# PRG_v2_0.net
KiCad netlist of a schematic drawn in Altium Designer
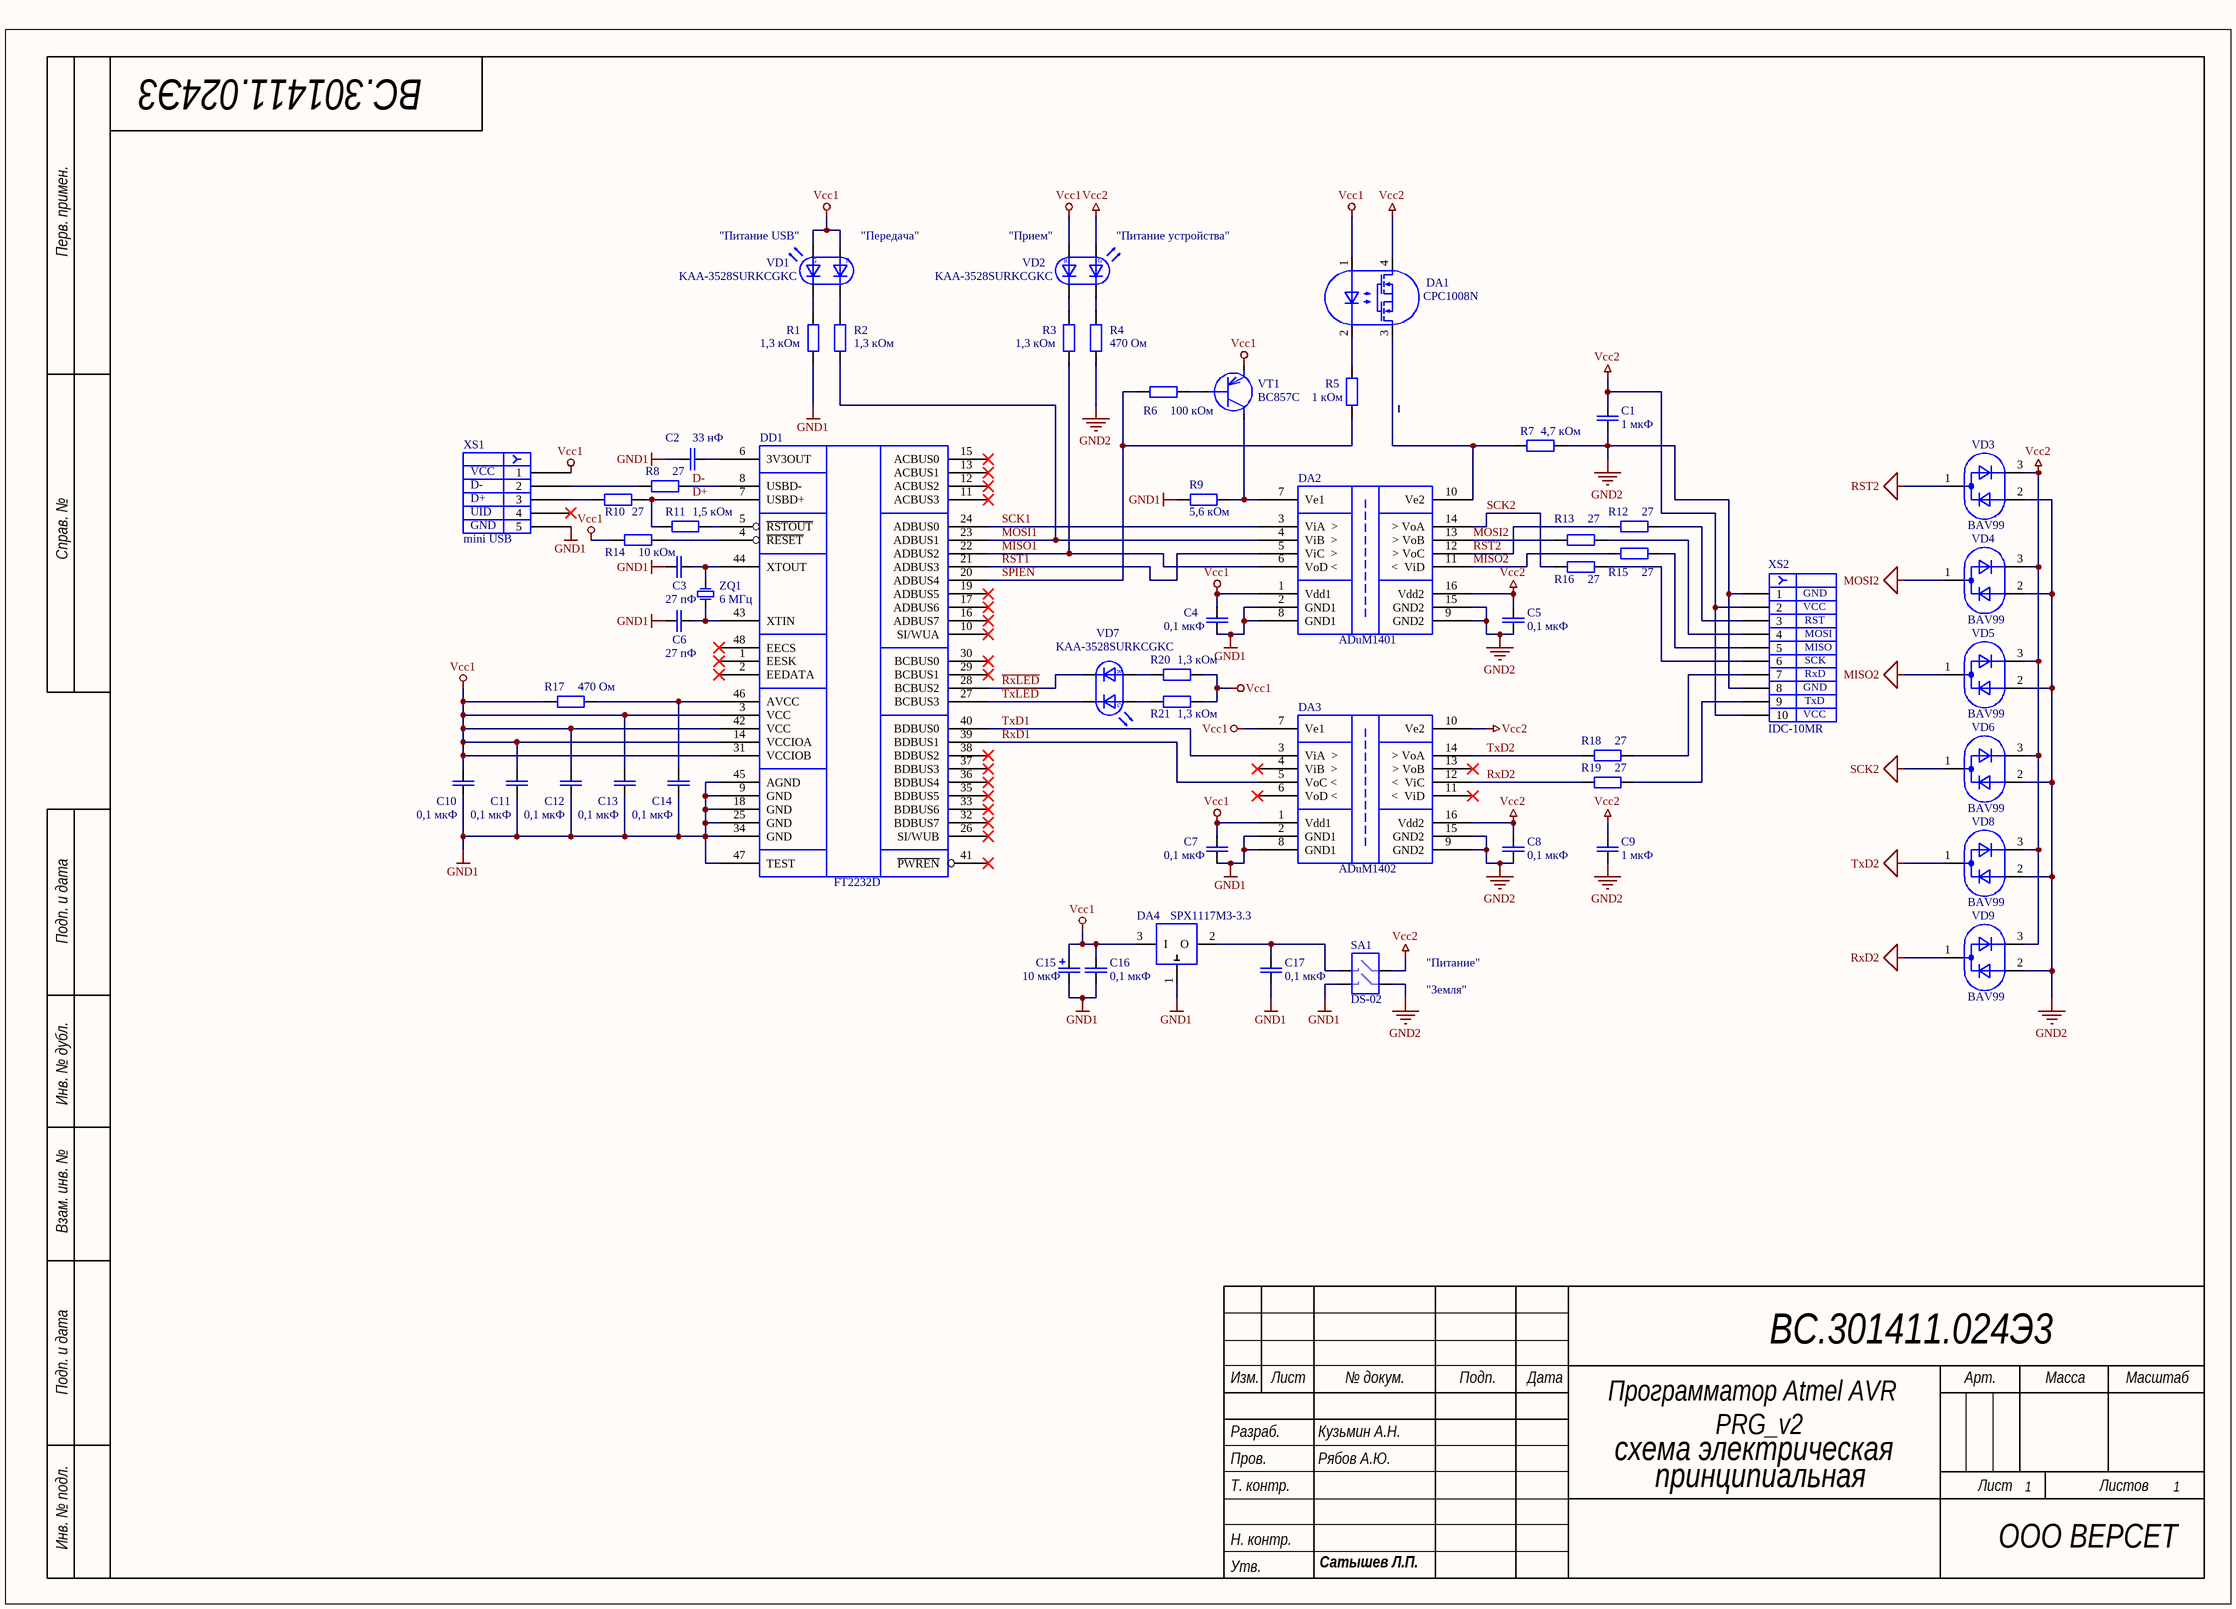
[diagram p0: PRG_v2.0.SchDoc]

(export (version "E")
  (design (tool "Eeschema 10.0.6"))
  (components
    (comp (ref "C1")
      (value "Конденсатор")
      (footprint "0603")
      (fields (field (name "НОМИНАЛ") "1 мкФ"))
      (libsource (lib "AVR-2232V") (part "C"))
    )
    (comp (ref "C2")
      (value "Конденсатор")
      (footprint "0603")
      (fields (field (name "НОМИНАЛ") "33 нФ"))
      (libsource (lib "AVR-2232V") (part "C"))
    )
    (comp (ref "C3")
      (value "Конденсатор")
      (footprint "0603")
      (fields (field (name "НОМИНАЛ") "27 пФ"))
      (libsource (lib "AVR-2232V") (part "C"))
    )
    (comp (ref "C4")
      (value "Конденсатор")
      (footprint "0603")
      (fields (field (name "НОМИНАЛ") "0,1 мкФ"))
      (libsource (lib "AVR-2232V") (part "C"))
    )
    (comp (ref "C5")
      (value "Конденсатор")
      (footprint "0603")
      (fields (field (name "НОМИНАЛ") "0,1 мкФ"))
      (libsource (lib "AVR-2232V") (part "C"))
    )
    (comp (ref "C6")
      (value "Конденсатор")
      (footprint "0603")
      (fields (field (name "НОМИНАЛ") "27 пФ"))
      (libsource (lib "AVR-2232V") (part "C"))
    )
    (comp (ref "C7")
      (value "Конденсатор")
      (footprint "0603")
      (fields (field (name "НОМИНАЛ") "0,1 мкФ"))
      (libsource (lib "AVR-2232V") (part "C"))
    )
    (comp (ref "C8")
      (value "Конденсатор")
      (footprint "0603")
      (fields (field (name "НОМИНАЛ") "0,1 мкФ"))
      (libsource (lib "AVR-2232V") (part "C"))
    )
    (comp (ref "C9")
      (value "Конденсатор")
      (footprint "0603")
      (fields (field (name "НОМИНАЛ") "1 мкФ"))
      (libsource (lib "AVR-2232V") (part "C"))
    )
    (comp (ref "C10")
      (value "Конденсатор")
      (footprint "0603")
      (fields (field (name "НОМИНАЛ") "0,1 мкФ"))
      (libsource (lib "AVR-2232V") (part "C"))
    )
    (comp (ref "C11")
      (value "Конденсатор")
      (footprint "0603")
      (fields (field (name "НОМИНАЛ") "0,1 мкФ"))
      (libsource (lib "AVR-2232V") (part "C"))
    )
    (comp (ref "C12")
      (value "Конденсатор")
      (footprint "0603")
      (fields (field (name "НОМИНАЛ") "0,1 мкФ"))
      (libsource (lib "AVR-2232V") (part "C"))
    )
    (comp (ref "C13")
      (value "Конденсатор")
      (footprint "0603")
      (fields (field (name "НОМИНАЛ") "0,1 мкФ"))
      (libsource (lib "AVR-2232V") (part "C"))
    )
    (comp (ref "C14")
      (value "Конденсатор")
      (footprint "0603")
      (fields (field (name "НОМИНАЛ") "0,1 мкФ"))
      (libsource (lib "AVR-2232V") (part "C"))
    )
    (comp (ref "C15")
      (value "Конденсатор электролитический")
      (footprint "C+A")
      (fields (field (name "НОМИНАЛ") "10 мкФ"))
      (libsource (lib "AVR-2232V") (part "C+"))
    )
    (comp (ref "C16")
      (value "Конденсатор")
      (footprint "0603")
      (fields (field (name "НОМИНАЛ") "0,1 мкФ"))
      (libsource (lib "AVR-2232V") (part "C"))
    )
    (comp (ref "C17")
      (value "Конденсатор")
      (footprint "0603")
      (fields (field (name "НОМИНАЛ") "0,1 мкФ"))
      (libsource (lib "AVR-2232V") (part "C"))
    )
    (comp (ref "DA1")
      (value "Оптопара")
      (footprint "SOIC4")
      (description "Оптореле")
      (libsource (lib "AVR-2232V") (part "CPC1008N"))
    )
    (comp (ref "DA2")
      (value "Буфер с гальванической разв зкой")
      (footprint "SOIC16")
      (libsource (lib "AVR-2232V") (part "ADuM1401"))
    )
    (comp (ref "DA3")
      (value "Буфер с гальванической разв зкой")
      (footprint "SOIC16")
      (libsource (lib "AVR-2232V") (part "ADuM1402"))
    )
    (comp (ref "DA4")
      (value "Стабилизатор напр жени ")
      (footprint "SOT223")
      (fields (field (name "TYPE") "SPX1117M3-3.3"))
      (libsource (lib "AVR-2232V") (part "VREG"))
    )
    (comp (ref "DD1")
      (value "Dual USB to Serial UART/FIFO IC")
      (footprint "LQFP48")
      (libsource (lib "AVR-2232V") (part "FT2232D"))
    )
    (comp (ref "R1")
      (value "Резистор")
      (footprint "0603")
      (fields (field (name "НОМИНАЛ") "1,3 кОм"))
      (libsource (lib "AVR-2232V") (part "R"))
    )
    (comp (ref "R2")
      (value "Резистор")
      (footprint "0603")
      (fields (field (name "НОМИНАЛ") "1,3 кОм"))
      (libsource (lib "AVR-2232V") (part "R"))
    )
    (comp (ref "R3")
      (value "Резистор")
      (footprint "0603")
      (fields (field (name "НОМИНАЛ") "1,3 кОм"))
      (libsource (lib "AVR-2232V") (part "R"))
    )
    (comp (ref "R4")
      (value "Резистор")
      (footprint "0603")
      (fields (field (name "НОМИНАЛ") "470 Ом"))
      (libsource (lib "AVR-2232V") (part "R"))
    )
    (comp (ref "R5")
      (value "Резистор")
      (footprint "0603")
      (fields (field (name "НОМИНАЛ") "1 кОм"))
      (libsource (lib "AVR-2232V") (part "R"))
    )
    (comp (ref "R6")
      (value "Резистор")
      (footprint "0603")
      (fields (field (name "НОМИНАЛ") "100 кОм"))
      (libsource (lib "AVR-2232V") (part "R"))
    )
    (comp (ref "R7")
      (value "Резистор")
      (footprint "0603")
      (fields (field (name "НОМИНАЛ") "4,7 кОм"))
      (libsource (lib "AVR-2232V") (part "R"))
    )
    (comp (ref "R8")
      (value "Резистор")
      (footprint "0603")
      (fields (field (name "НОМИНАЛ") "27"))
      (libsource (lib "AVR-2232V") (part "R"))
    )
    (comp (ref "R9")
      (value "Резистор")
      (footprint "0603")
      (fields (field (name "НОМИНАЛ") "5,6 кОм"))
      (libsource (lib "AVR-2232V") (part "R"))
    )
    (comp (ref "R10")
      (value "Резистор")
      (footprint "0603")
      (fields (field (name "НОМИНАЛ") "27"))
      (libsource (lib "AVR-2232V") (part "R"))
    )
    (comp (ref "R11")
      (value "Резистор")
      (footprint "0603")
      (fields (field (name "НОМИНАЛ") "1,5 кОм"))
      (libsource (lib "AVR-2232V") (part "R"))
    )
    (comp (ref "R12")
      (value "Резистор")
      (footprint "0603")
      (fields (field (name "НОМИНАЛ") "27"))
      (libsource (lib "AVR-2232V") (part "R"))
    )
    (comp (ref "R13")
      (value "Резистор")
      (footprint "0603")
      (fields (field (name "НОМИНАЛ") "27"))
      (libsource (lib "AVR-2232V") (part "R"))
    )
    (comp (ref "R14")
      (value "Резистор")
      (footprint "0603")
      (fields (field (name "НОМИНАЛ") "10 кОм"))
      (libsource (lib "AVR-2232V") (part "R"))
    )
    (comp (ref "R15")
      (value "Резистор")
      (footprint "0603")
      (fields (field (name "НОМИНАЛ") "27"))
      (libsource (lib "AVR-2232V") (part "R"))
    )
    (comp (ref "R16")
      (value "Резистор")
      (footprint "0603")
      (fields (field (name "НОМИНАЛ") "27"))
      (libsource (lib "AVR-2232V") (part "R"))
    )
    (comp (ref "R17")
      (value "Резистор")
      (footprint "0603")
      (fields (field (name "НОМИНАЛ") "470 Ом"))
      (libsource (lib "AVR-2232V") (part "R"))
    )
    (comp (ref "R18")
      (value "Резистор")
      (footprint "0603")
      (fields (field (name "НОМИНАЛ") "27"))
      (libsource (lib "AVR-2232V") (part "R"))
    )
    (comp (ref "R19")
      (value "Резистор")
      (footprint "0603")
      (fields (field (name "НОМИНАЛ") "27"))
      (libsource (lib "AVR-2232V") (part "R"))
    )
    (comp (ref "R20")
      (value "Резистор")
      (footprint "0603")
      (fields (field (name "НОМИНАЛ") "1,3 кОм"))
      (libsource (lib "AVR-2232V") (part "R"))
    )
    (comp (ref "R21")
      (value "Резистор")
      (footprint "0603")
      (fields (field (name "НОМИНАЛ") "1,3 кОм"))
      (libsource (lib "AVR-2232V") (part "R"))
    )
    (comp (ref "SA1")
      (value "Микропереключатель")
      (footprint "DS-02")
      (fields (field (name "ТИП") "DS-02"))
      (libsource (lib "AVR-2232V") (part "DS-02"))
    )
    (comp (ref "VD1")
      (value "Светодиод двухцветный")
      (footprint "KAA-3528SURKCGKC")
      (fields (field (name "ТИП") "KAA-3528SURKCGKC"))
      (libsource (lib "AVR-2232V") (part "Светодиод RG"))
    )
    (comp (ref "VD2")
      (value "Светодиод двухцветный")
      (footprint "KAA-3528SURKCGKC")
      (fields (field (name "ТИП") "KAA-3528SURKCGKC"))
      (libsource (lib "") (part "Светодиод RG_1"))
    )
    (comp (ref "VD3")
      (value "Пара защитный диодов Шоттки")
      (footprint "SOT23")
      (libsource (lib "AVR-2232V") (part "BAV99"))
    )
    (comp (ref "VD4")
      (value "Пара защитный диодов Шоттки")
      (footprint "SOT23")
      (libsource (lib "AVR-2232V") (part "BAV99"))
    )
    (comp (ref "VD5")
      (value "Пара защитный диодов Шоттки")
      (footprint "SOT23")
      (libsource (lib "AVR-2232V") (part "BAV99"))
    )
    (comp (ref "VD6")
      (value "Пара защитный диодов Шоттки")
      (footprint "SOT23")
      (libsource (lib "AVR-2232V") (part "BAV99"))
    )
    (comp (ref "VD7")
      (value "Светодиод двухцветный")
      (footprint "KAA-3528SURKCGKC")
      (fields (field (name "ТИП") "KAA-3528SURKCGKC"))
      (libsource (lib "") (part "Светодиод RG_1"))
    )
    (comp (ref "VD8")
      (value "Пара защитный диодов Шоттки")
      (footprint "SOT23")
      (libsource (lib "AVR-2232V") (part "BAV99"))
    )
    (comp (ref "VD9")
      (value "Пара защитный диодов Шоттки")
      (footprint "SOT23")
      (libsource (lib "AVR-2232V") (part "BAV99"))
    )
    (comp (ref "VT1")
      (value "Транзистор pnp")
      (footprint "SOT23")
      (fields (field (name "TYPE") "BC857C"))
      (libsource (lib "AVR-2232V") (part "PNP"))
    )
    (comp (ref "XS1")
      (value "Разъем мини-USB")
      (footprint "mini USB A")
      (libsource (lib "AVR-2232V") (part "miniUSB"))
    )
    (comp (ref "XS2")
      (value "IDC-10MR")
      (footprint "IDC-10MR")
      (fields (field (name "ТИП") "IDC-10MR"))
      (libsource (lib "AVR-2232V") (part "IDC-10MR"))
    )
    (comp (ref "ZQ1")
      (value "Кварцевый резонатор")
      (footprint "HC49-SM")
      (fields (field (name "НОМИНАЛ") "6 МГц"))
      (libsource (lib "AVR-2232V") (part "ZQ"))
    )
  )
  (nets
    (net (code "1") (name "/D+") (class "Default")
      (node (ref "DD1") (pin "7") (pinfunction "USBD+_7") (pintype "passive"))
      (node (ref "R10") (pin "2") (pinfunction "2_2") (pintype "passive"))
      (node (ref "R11") (pin "1") (pinfunction "1_1") (pintype "passive"))
    )
    (net (code "2") (name "/D-") (class "Default")
      (node (ref "DD1") (pin "8") (pinfunction "USBD-_8") (pintype "passive"))
      (node (ref "R8") (pin "2") (pinfunction "2_2") (pintype "passive"))
    )
    (net (code "3") (name "/MISO1") (class "Default")
      (node (ref "DA2") (pin "6") (pinfunction "VoD_<_6") (pintype "passive"))
      (node (ref "DD1") (pin "22") (pinfunction "ADBUS2_22") (pintype "passive"))
      (node (ref "R3") (pin "1") (pinfunction "1_1") (pintype "passive"))
    )
    (net (code "4") (name "/MOSI1") (class "Default")
      (node (ref "DA2") (pin "4") (pinfunction "ViB__>_4") (pintype "passive"))
      (node (ref "DD1") (pin "23") (pinfunction "ADBUS1_23") (pintype "passive"))
      (node (ref "R2") (pin "1") (pinfunction "1_1") (pintype "passive"))
    )
    (net (code "5") (name "/RxD1") (class "Default")
      (node (ref "DA3") (pin "5") (pinfunction "VoC_<_5") (pintype "passive"))
      (node (ref "DD1") (pin "39") (pinfunction "BDBUS1_39") (pintype "passive"))
    )
    (net (code "6") (name "/SCK1") (class "Default")
      (node (ref "DA2") (pin "3") (pinfunction "ViA__>_3") (pintype "passive"))
      (node (ref "DD1") (pin "24") (pinfunction "ADBUS0_24") (pintype "passive"))
    )
    (net (code "7") (name "/TxD1") (class "Default")
      (node (ref "DA3") (pin "3") (pinfunction "ViA__>_3") (pintype "passive"))
      (node (ref "DD1") (pin "40") (pinfunction "BDBUS0_40") (pintype "passive"))
    )
    (net (code "8") (name "/~{RST}1") (class "Default")
      (node (ref "DA2") (pin "5") (pinfunction "ViC__>_5") (pintype "passive"))
      (node (ref "DD1") (pin "21") (pinfunction "ADBUS3_21") (pintype "passive"))
    )
    (net (code "9") (name "/~{RxLED}") (class "Default")
      (node (ref "DD1") (pin "28") (pinfunction "BCBUS2_28") (pintype "passive"))
      (node (ref "VD7") (pin "1") (pinfunction "1_1") (pintype "passive"))
    )
    (net (code "10") (name "/~{SPIEN}") (class "Default")
      (node (ref "DD1") (pin "20") (pinfunction "ADBUS4_20") (pintype "passive"))
      (node (ref "R5") (pin "1") (pinfunction "1_1") (pintype "passive"))
      (node (ref "R6") (pin "2") (pinfunction "2_2") (pintype "passive"))
    )
    (net (code "11") (name "/~{TxLED}") (class "Default")
      (node (ref "DD1") (pin "27") (pinfunction "BCBUS3_27") (pintype "passive"))
      (node (ref "VD7") (pin "3") (pinfunction "3_3") (pintype "passive"))
    )
    (net (code "12") (name "GND1") (class "Default")
      (node (ref "C10") (pin "2") (pinfunction "2_2") (pintype "passive"))
      (node (ref "C11") (pin "2") (pinfunction "2_2") (pintype "passive"))
      (node (ref "C12") (pin "2") (pinfunction "2_2") (pintype "passive"))
      (node (ref "C13") (pin "2") (pinfunction "2_2") (pintype "passive"))
      (node (ref "C14") (pin "2") (pinfunction "2_2") (pintype "passive"))
      (node (ref "C15") (pin "2") (pinfunction "2_2") (pintype "passive"))
      (node (ref "C16") (pin "1") (pinfunction "1_1") (pintype "passive"))
      (node (ref "C17") (pin "1") (pinfunction "1_1") (pintype "passive"))
      (node (ref "C2") (pin "1") (pinfunction "1_1") (pintype "passive"))
      (node (ref "C3") (pin "1") (pinfunction "1_1") (pintype "passive"))
      (node (ref "C4") (pin "1") (pinfunction "1_1") (pintype "passive"))
      (node (ref "C6") (pin "1") (pinfunction "1_1") (pintype "passive"))
      (node (ref "C7") (pin "1") (pinfunction "1_1") (pintype "passive"))
      (node (ref "DA2") (pin "2") (pinfunction "GND1_2") (pintype "passive"))
      (node (ref "DA2") (pin "8") (pinfunction "GND1_8") (pintype "passive"))
      (node (ref "DA3") (pin "2") (pinfunction "GND1_2") (pintype "passive"))
      (node (ref "DA3") (pin "8") (pinfunction "GND1_8") (pintype "passive"))
      (node (ref "DA4") (pin "1") (pinfunction "GND_1") (pintype "passive"))
      (node (ref "DD1") (pin "18") (pinfunction "GND_18") (pintype "passive"))
      (node (ref "DD1") (pin "25") (pinfunction "GND_25") (pintype "passive"))
      (node (ref "DD1") (pin "34") (pinfunction "GND_34") (pintype "passive"))
      (node (ref "DD1") (pin "45") (pinfunction "AGND_45") (pintype "passive"))
      (node (ref "DD1") (pin "47") (pinfunction "TEST_47") (pintype "passive"))
      (node (ref "DD1") (pin "9") (pinfunction "GND_9") (pintype "passive"))
      (node (ref "R1") (pin "1") (pinfunction "1_1") (pintype "passive"))
      (node (ref "R9") (pin "2") (pinfunction "2_2") (pintype "passive"))
      (node (ref "SA1") (pin "4") (pinfunction "4_4") (pintype "passive"))
      (node (ref "XS1") (pin "5") (pinfunction "5_5") (pintype "passive"))
    )
    (net (code "13") (name "GND2") (class "Default")
      (node (ref "C1") (pin "1") (pinfunction "1_1") (pintype "passive"))
      (node (ref "C5") (pin "1") (pinfunction "1_1") (pintype "passive"))
      (node (ref "C8") (pin "1") (pinfunction "1_1") (pintype "passive"))
      (node (ref "C9") (pin "1") (pinfunction "1_1") (pintype "passive"))
      (node (ref "DA2") (pin "15") (pinfunction "GND2_15") (pintype "passive"))
      (node (ref "DA2") (pin "9") (pinfunction "GND2_9") (pintype "passive"))
      (node (ref "DA3") (pin "15") (pinfunction "GND2_15") (pintype "passive"))
      (node (ref "DA3") (pin "9") (pinfunction "GND2_9") (pintype "passive"))
      (node (ref "R4") (pin "2") (pinfunction "2_2") (pintype "passive"))
      (node (ref "R7") (pin "1") (pinfunction "1_1") (pintype "passive"))
      (node (ref "SA1") (pin "2") (pinfunction "2_2") (pintype "passive"))
      (node (ref "VD3") (pin "2") (pinfunction "2_2") (pintype "passive"))
      (node (ref "VD4") (pin "2") (pinfunction "2_2") (pintype "passive"))
      (node (ref "VD5") (pin "2") (pinfunction "2_2") (pintype "passive"))
      (node (ref "VD6") (pin "2") (pinfunction "2_2") (pintype "passive"))
      (node (ref "VD8") (pin "2") (pinfunction "2_2") (pintype "passive"))
      (node (ref "VD9") (pin "2") (pinfunction "2_2") (pintype "passive"))
      (node (ref "XS2") (pin "1") (pinfunction "1_1") (pintype "passive"))
      (node (ref "XS2") (pin "8") (pinfunction "8_8") (pintype "passive"))
    )
    (net (code "14") (name "MISO2") (class "Default")
      (node (ref "DA2") (pin "11") (pinfunction "<__ViD_11") (pintype "passive"))
      (node (ref "R15") (pin "1") (pinfunction "1_1") (pintype "passive"))
      (node (ref "VD5") (pin "1") (pinfunction "1_1") (pintype "passive"))
    )
    (net (code "15") (name "MOSI2") (class "Default")
      (node (ref "DA2") (pin "13") (pinfunction ">_VoB_13") (pintype "passive"))
      (node (ref "R13") (pin "1") (pinfunction "1_1") (pintype "passive"))
      (node (ref "VD4") (pin "1") (pinfunction "1_1") (pintype "passive"))
    )
    (net (code "16") (name "Net-(DA1-E)") (class "Default")
      (node (ref "DA1") (pin "3") (pinfunction "E_3") (pintype "passive"))
      (node (ref "DA2") (pin "10") (pinfunction "Ve2_10") (pintype "passive"))
      (node (ref "R7") (pin "2") (pinfunction "2_2") (pintype "passive"))
    )
    (net (code "17") (name "Net-(DA1-K)") (class "Default")
      (node (ref "DA1") (pin "2") (pinfunction "K_2") (pintype "passive"))
      (node (ref "R5") (pin "2") (pinfunction "2_2") (pintype "passive"))
    )
    (net (code "18") (name "Net-(DA2-Ve1)") (class "Default")
      (node (ref "DA2") (pin "7") (pinfunction "Ve1_7") (pintype "passive"))
      (node (ref "R9") (pin "1") (pinfunction "1_1") (pintype "passive"))
      (node (ref "VT1") (pin "1") (pinfunction "Collector_1") (pintype "passive"))
    )
    (net (code "19") (name "Net-(DA4-O)") (class "Default")
      (node (ref "C17") (pin "2") (pinfunction "2_2") (pintype "passive"))
      (node (ref "DA4") (pin "2") (pinfunction "O_2") (pintype "passive"))
      (node (ref "SA1") (pin "3") (pinfunction "3_3") (pintype "passive"))
    )
    (net (code "20") (name "Net-(DD1-3V3OUT)") (class "Default")
      (node (ref "C2") (pin "2") (pinfunction "2_2") (pintype "passive"))
      (node (ref "DD1") (pin "6") (pinfunction "3V3OUT_6") (pintype "passive"))
    )
    (net (code "21") (name "Net-(DD1-AVCC)") (class "Default")
      (node (ref "C14") (pin "1") (pinfunction "1_1") (pintype "passive"))
      (node (ref "DD1") (pin "46") (pinfunction "AVCC_46") (pintype "passive"))
      (node (ref "R17") (pin "2") (pinfunction "2_2") (pintype "passive"))
    )
    (net (code "22") (name "Net-(DD1-XTIN)") (class "Default")
      (node (ref "C6") (pin "2") (pinfunction "2_2") (pintype "passive"))
      (node (ref "DD1") (pin "43") (pinfunction "XTIN_43") (pintype "passive"))
      (node (ref "ZQ1") (pin "1") (pinfunction "1_1") (pintype "passive"))
    )
    (net (code "23") (name "Net-(DD1-XTOUT)") (class "Default")
      (node (ref "C3") (pin "2") (pinfunction "2_2") (pintype "passive"))
      (node (ref "DD1") (pin "44") (pinfunction "XTOUT_44") (pintype "passive"))
      (node (ref "ZQ1") (pin "2") (pinfunction "2_2") (pintype "passive"))
    )
    (net (code "24") (name "Net-(DD1-~{RESET})") (class "Default")
      (node (ref "DD1") (pin "4") (pinfunction "~{RESET}_4") (pintype "passive"))
      (node (ref "R14") (pin "2") (pinfunction "2_2") (pintype "passive"))
    )
    (net (code "25") (name "Net-(DD1-~{RSTOUT})") (class "Default")
      (node (ref "DD1") (pin "5") (pinfunction "~{RSTOUT}_5") (pintype "passive"))
      (node (ref "R11") (pin "2") (pinfunction "2_2") (pintype "passive"))
    )
    (net (code "26") (name "Net-(R1-Pad2)") (class "Default")
      (node (ref "R1") (pin "2") (pinfunction "2_2") (pintype "passive"))
      (node (ref "VD1") (pin "3") (pinfunction "3_3") (pintype "passive"))
    )
    (net (code "27") (name "Net-(R2-Pad2)") (class "Default")
      (node (ref "R2") (pin "2") (pinfunction "2_2") (pintype "passive"))
      (node (ref "VD1") (pin "1") (pinfunction "1_1") (pintype "passive"))
    )
    (net (code "28") (name "Net-(R3-Pad2)") (class "Default")
      (node (ref "R3") (pin "2") (pinfunction "2_2") (pintype "passive"))
      (node (ref "VD2") (pin "1") (pinfunction "1_1") (pintype "passive"))
    )
    (net (code "29") (name "Net-(R4-Pad1)") (class "Default")
      (node (ref "R4") (pin "1") (pinfunction "1_1") (pintype "passive"))
      (node (ref "VD2") (pin "3") (pinfunction "3_3") (pintype "passive"))
    )
    (net (code "30") (name "Net-(R8-Pad1)") (class "Default")
      (node (ref "R8") (pin "1") (pinfunction "1_1") (pintype "passive"))
      (node (ref "XS1") (pin "2") (pinfunction "2_2") (pintype "passive"))
    )
    (net (code "31") (name "Net-(R10-Pad1)") (class "Default")
      (node (ref "R10") (pin "1") (pinfunction "1_1") (pintype "passive"))
      (node (ref "XS1") (pin "3") (pinfunction "3_3") (pintype "passive"))
    )
    (net (code "32") (name "Net-(R12-Pad2)") (class "Default")
      (node (ref "R12") (pin "2") (pinfunction "2_2") (pintype "passive"))
      (node (ref "XS2") (pin "3") (pinfunction "3_3") (pintype "passive"))
    )
    (net (code "33") (name "Net-(R13-Pad2)") (class "Default")
      (node (ref "R13") (pin "2") (pinfunction "2_2") (pintype "passive"))
      (node (ref "XS2") (pin "4") (pinfunction "4_4") (pintype "passive"))
    )
    (net (code "34") (name "Net-(R15-Pad2)") (class "Default")
      (node (ref "R15") (pin "2") (pinfunction "2_2") (pintype "passive"))
      (node (ref "XS2") (pin "5") (pinfunction "5_5") (pintype "passive"))
    )
    (net (code "35") (name "Net-(R16-Pad2)") (class "Default")
      (node (ref "R16") (pin "2") (pinfunction "2_2") (pintype "passive"))
      (node (ref "XS2") (pin "6") (pinfunction "6_6") (pintype "passive"))
    )
    (net (code "36") (name "Net-(R18-Pad2)") (class "Default")
      (node (ref "R18") (pin "2") (pinfunction "2_2") (pintype "passive"))
      (node (ref "XS2") (pin "7") (pinfunction "7_7") (pintype "passive"))
    )
    (net (code "37") (name "Net-(R19-Pad2)") (class "Default")
      (node (ref "R19") (pin "2") (pinfunction "2_2") (pintype "passive"))
      (node (ref "XS2") (pin "9") (pinfunction "9_9") (pintype "passive"))
    )
    (net (code "38") (name "Net-(R20-Pad2)") (class "Default")
      (node (ref "R20") (pin "2") (pinfunction "2_2") (pintype "passive"))
      (node (ref "VD7") (pin "2") (pinfunction "2_2") (pintype "passive"))
    )
    (net (code "39") (name "Net-(R21-Pad2)") (class "Default")
      (node (ref "R21") (pin "2") (pinfunction "2_2") (pintype "passive"))
      (node (ref "VD7") (pin "4") (pinfunction "4_4") (pintype "passive"))
    )
    (net (code "40") (name "Net-(VT1-Base)") (class "Default")
      (node (ref "R6") (pin "1") (pinfunction "1_1") (pintype "passive"))
      (node (ref "VT1") (pin "2") (pinfunction "Base_2") (pintype "passive"))
    )
    (net (code "41") (name "RST2") (class "Default")
      (node (ref "DA2") (pin "12") (pinfunction ">_VoC_12") (pintype "passive"))
      (node (ref "R12") (pin "1") (pinfunction "1_1") (pintype "passive"))
      (node (ref "VD3") (pin "1") (pinfunction "1_1") (pintype "passive"))
    )
    (net (code "42") (name "RxD2") (class "Default")
      (node (ref "DA3") (pin "12") (pinfunction "<__ViC_12") (pintype "passive"))
      (node (ref "R19") (pin "1") (pinfunction "1_1") (pintype "passive"))
      (node (ref "VD9") (pin "1") (pinfunction "1_1") (pintype "passive"))
    )
    (net (code "43") (name "SCK2") (class "Default")
      (node (ref "DA2") (pin "14") (pinfunction ">_VoA_14") (pintype "passive"))
      (node (ref "R16") (pin "1") (pinfunction "1_1") (pintype "passive"))
      (node (ref "VD6") (pin "1") (pinfunction "1_1") (pintype "passive"))
    )
    (net (code "44") (name "TxD2") (class "Default")
      (node (ref "DA3") (pin "14") (pinfunction ">_VoA_14") (pintype "passive"))
      (node (ref "R18") (pin "1") (pinfunction "1_1") (pintype "passive"))
      (node (ref "VD8") (pin "1") (pinfunction "1_1") (pintype "passive"))
    )
    (net (code "45") (name "Vcc1") (class "Default")
      (node (ref "C10") (pin "1") (pinfunction "1_1") (pintype "passive"))
      (node (ref "C11") (pin "1") (pinfunction "1_1") (pintype "passive"))
      (node (ref "C12") (pin "1") (pinfunction "1_1") (pintype "passive"))
      (node (ref "C13") (pin "1") (pinfunction "1_1") (pintype "passive"))
      (node (ref "C15") (pin "1") (pinfunction "1_1") (pintype "passive"))
      (node (ref "C16") (pin "2") (pinfunction "2_2") (pintype "passive"))
      (node (ref "C4") (pin "2") (pinfunction "2_2") (pintype "passive"))
      (node (ref "C7") (pin "2") (pinfunction "2_2") (pintype "passive"))
      (node (ref "DA1") (pin "1") (pinfunction "A_1") (pintype "passive"))
      (node (ref "DA2") (pin "1") (pinfunction "Vdd1_1") (pintype "passive"))
      (node (ref "DA3") (pin "1") (pinfunction "Vdd1_1") (pintype "passive"))
      (node (ref "DA3") (pin "7") (pinfunction "Ve1_7") (pintype "passive"))
      (node (ref "DA4") (pin "3") (pinfunction "I_3") (pintype "passive"))
      (node (ref "DD1") (pin "14") (pinfunction "VCCIOA_14") (pintype "passive"))
      (node (ref "DD1") (pin "3") (pinfunction "VCC_3") (pintype "passive"))
      (node (ref "DD1") (pin "31") (pinfunction "VCCIOB_31") (pintype "passive"))
      (node (ref "DD1") (pin "42") (pinfunction "VCC_42") (pintype "passive"))
      (node (ref "R14") (pin "1") (pinfunction "1_1") (pintype "passive"))
      (node (ref "R17") (pin "1") (pinfunction "1_1") (pintype "passive"))
      (node (ref "R20") (pin "1") (pinfunction "1_1") (pintype "passive"))
      (node (ref "R21") (pin "1") (pinfunction "1_1") (pintype "passive"))
      (node (ref "VD1") (pin "2") (pinfunction "2_2") (pintype "passive"))
      (node (ref "VD1") (pin "4") (pinfunction "4_4") (pintype "passive"))
      (node (ref "VD2") (pin "2") (pinfunction "2_2") (pintype "passive"))
      (node (ref "VT1") (pin "3") (pinfunction "Emitter_3") (pintype "passive"))
      (node (ref "XS1") (pin "1") (pinfunction "1_1") (pintype "passive"))
    )
    (net (code "46") (name "Vcc2") (class "Default")
      (node (ref "C1") (pin "2") (pinfunction "2_2") (pintype "passive"))
      (node (ref "C5") (pin "2") (pinfunction "2_2") (pintype "passive"))
      (node (ref "C8") (pin "2") (pinfunction "2_2") (pintype "passive"))
      (node (ref "C9") (pin "2") (pinfunction "2_2") (pintype "passive"))
      (node (ref "DA1") (pin "4") (pinfunction "C_4") (pintype "passive"))
      (node (ref "DA2") (pin "16") (pinfunction "Vdd2_16") (pintype "passive"))
      (node (ref "DA3") (pin "10") (pinfunction "Ve2_10") (pintype "passive"))
      (node (ref "DA3") (pin "16") (pinfunction "Vdd2_16") (pintype "passive"))
      (node (ref "SA1") (pin "1") (pinfunction "1_1") (pintype "passive"))
      (node (ref "VD2") (pin "4") (pinfunction "4_4") (pintype "passive"))
      (node (ref "VD3") (pin "3") (pinfunction "3_3") (pintype "passive"))
      (node (ref "VD4") (pin "3") (pinfunction "3_3") (pintype "passive"))
      (node (ref "VD5") (pin "3") (pinfunction "3_3") (pintype "passive"))
      (node (ref "VD6") (pin "3") (pinfunction "3_3") (pintype "passive"))
      (node (ref "VD8") (pin "3") (pinfunction "3_3") (pintype "passive"))
      (node (ref "VD9") (pin "3") (pinfunction "3_3") (pintype "passive"))
      (node (ref "XS2") (pin "10") (pinfunction "10_10") (pintype "passive"))
      (node (ref "XS2") (pin "2") (pinfunction "2_2") (pintype "passive"))
    )
    (net (code "47") (name "unconnected-(DA3-<__ViD-Pad11)") (class "Default")
      (node (ref "DA3") (pin "11") (pinfunction "<__ViD_11") (pintype "passive+no_connect"))
    )
    (net (code "48") (name "unconnected-(DA3->_VoB-Pad13)") (class "Default")
      (node (ref "DA3") (pin "13") (pinfunction ">_VoB_13") (pintype "passive+no_connect"))
    )
    (net (code "49") (name "unconnected-(DA3-ViB__>-Pad4)") (class "Default")
      (node (ref "DA3") (pin "4") (pinfunction "ViB__>_4") (pintype "passive+no_connect"))
    )
    (net (code "50") (name "unconnected-(DA3-VoD_<-Pad6)") (class "Default")
      (node (ref "DA3") (pin "6") (pinfunction "VoD_<_6") (pintype "passive+no_connect"))
    )
    (net (code "51") (name "unconnected-(DD1-ACBUS0-Pad15)") (class "Default")
      (node (ref "DD1") (pin "15") (pinfunction "ACBUS0_15") (pintype "passive+no_connect"))
    )
    (net (code "52") (name "unconnected-(DD1-ACBUS1-Pad13)") (class "Default")
      (node (ref "DD1") (pin "13") (pinfunction "ACBUS1_13") (pintype "passive+no_connect"))
    )
    (net (code "53") (name "unconnected-(DD1-ACBUS2-Pad12)") (class "Default")
      (node (ref "DD1") (pin "12") (pinfunction "ACBUS2_12") (pintype "passive+no_connect"))
    )
    (net (code "54") (name "unconnected-(DD1-ACBUS3-Pad11)") (class "Default")
      (node (ref "DD1") (pin "11") (pinfunction "ACBUS3_11") (pintype "passive+no_connect"))
    )
    (net (code "55") (name "unconnected-(DD1-ADBUS5-Pad19)") (class "Default")
      (node (ref "DD1") (pin "19") (pinfunction "ADBUS5_19") (pintype "passive+no_connect"))
    )
    (net (code "56") (name "unconnected-(DD1-ADBUS6-Pad17)") (class "Default")
      (node (ref "DD1") (pin "17") (pinfunction "ADBUS6_17") (pintype "passive+no_connect"))
    )
    (net (code "57") (name "unconnected-(DD1-ADBUS7-Pad16)") (class "Default")
      (node (ref "DD1") (pin "16") (pinfunction "ADBUS7_16") (pintype "passive+no_connect"))
    )
    (net (code "58") (name "unconnected-(DD1-BCBUS0-Pad30)") (class "Default")
      (node (ref "DD1") (pin "30") (pinfunction "BCBUS0_30") (pintype "passive+no_connect"))
    )
    (net (code "59") (name "unconnected-(DD1-BCBUS1-Pad29)") (class "Default")
      (node (ref "DD1") (pin "29") (pinfunction "BCBUS1_29") (pintype "passive+no_connect"))
    )
    (net (code "60") (name "unconnected-(DD1-BDBUS2-Pad38)") (class "Default")
      (node (ref "DD1") (pin "38") (pinfunction "BDBUS2_38") (pintype "passive+no_connect"))
    )
    (net (code "61") (name "unconnected-(DD1-BDBUS3-Pad37)") (class "Default")
      (node (ref "DD1") (pin "37") (pinfunction "BDBUS3_37") (pintype "passive+no_connect"))
    )
    (net (code "62") (name "unconnected-(DD1-BDBUS4-Pad36)") (class "Default")
      (node (ref "DD1") (pin "36") (pinfunction "BDBUS4_36") (pintype "passive+no_connect"))
    )
    (net (code "63") (name "unconnected-(DD1-BDBUS5-Pad35)") (class "Default")
      (node (ref "DD1") (pin "35") (pinfunction "BDBUS5_35") (pintype "passive+no_connect"))
    )
    (net (code "64") (name "unconnected-(DD1-BDBUS6-Pad33)") (class "Default")
      (node (ref "DD1") (pin "33") (pinfunction "BDBUS6_33") (pintype "passive+no_connect"))
    )
    (net (code "65") (name "unconnected-(DD1-BDBUS7-Pad32)") (class "Default")
      (node (ref "DD1") (pin "32") (pinfunction "BDBUS7_32") (pintype "passive+no_connect"))
    )
    (net (code "66") (name "unconnected-(DD1-EECS-Pad48)") (class "Default")
      (node (ref "DD1") (pin "48") (pinfunction "EECS_48") (pintype "passive+no_connect"))
    )
    (net (code "67") (name "unconnected-(DD1-EEDATA-Pad2)") (class "Default")
      (node (ref "DD1") (pin "2") (pinfunction "EEDATA_2") (pintype "passive+no_connect"))
    )
    (net (code "68") (name "unconnected-(DD1-EESK-Pad1)") (class "Default")
      (node (ref "DD1") (pin "1") (pinfunction "EESK_1") (pintype "passive+no_connect"))
    )
    (net (code "69") (name "unconnected-(DD1-SI{slash}WUA-Pad10)") (class "Default")
      (node (ref "DD1") (pin "10") (pinfunction "SI/WUA_10") (pintype "passive+no_connect"))
    )
    (net (code "70") (name "unconnected-(DD1-SI{slash}WUB-Pad26)") (class "Default")
      (node (ref "DD1") (pin "26") (pinfunction "SI/WUB_26") (pintype "passive+no_connect"))
    )
    (net (code "71") (name "unconnected-(DD1-~{PWREN}-Pad41)") (class "Default")
      (node (ref "DD1") (pin "41") (pinfunction "~{PWREN}_41") (pintype "passive+no_connect"))
    )
    (net (code "72") (name "unconnected-(XS1-Pad4)") (class "Default")
      (node (ref "XS1") (pin "4") (pinfunction "4_4") (pintype "passive+no_connect"))
    )
  )
)
